# HRV_Control.net
KiCad netlist of a schematic drawn in EAGLE
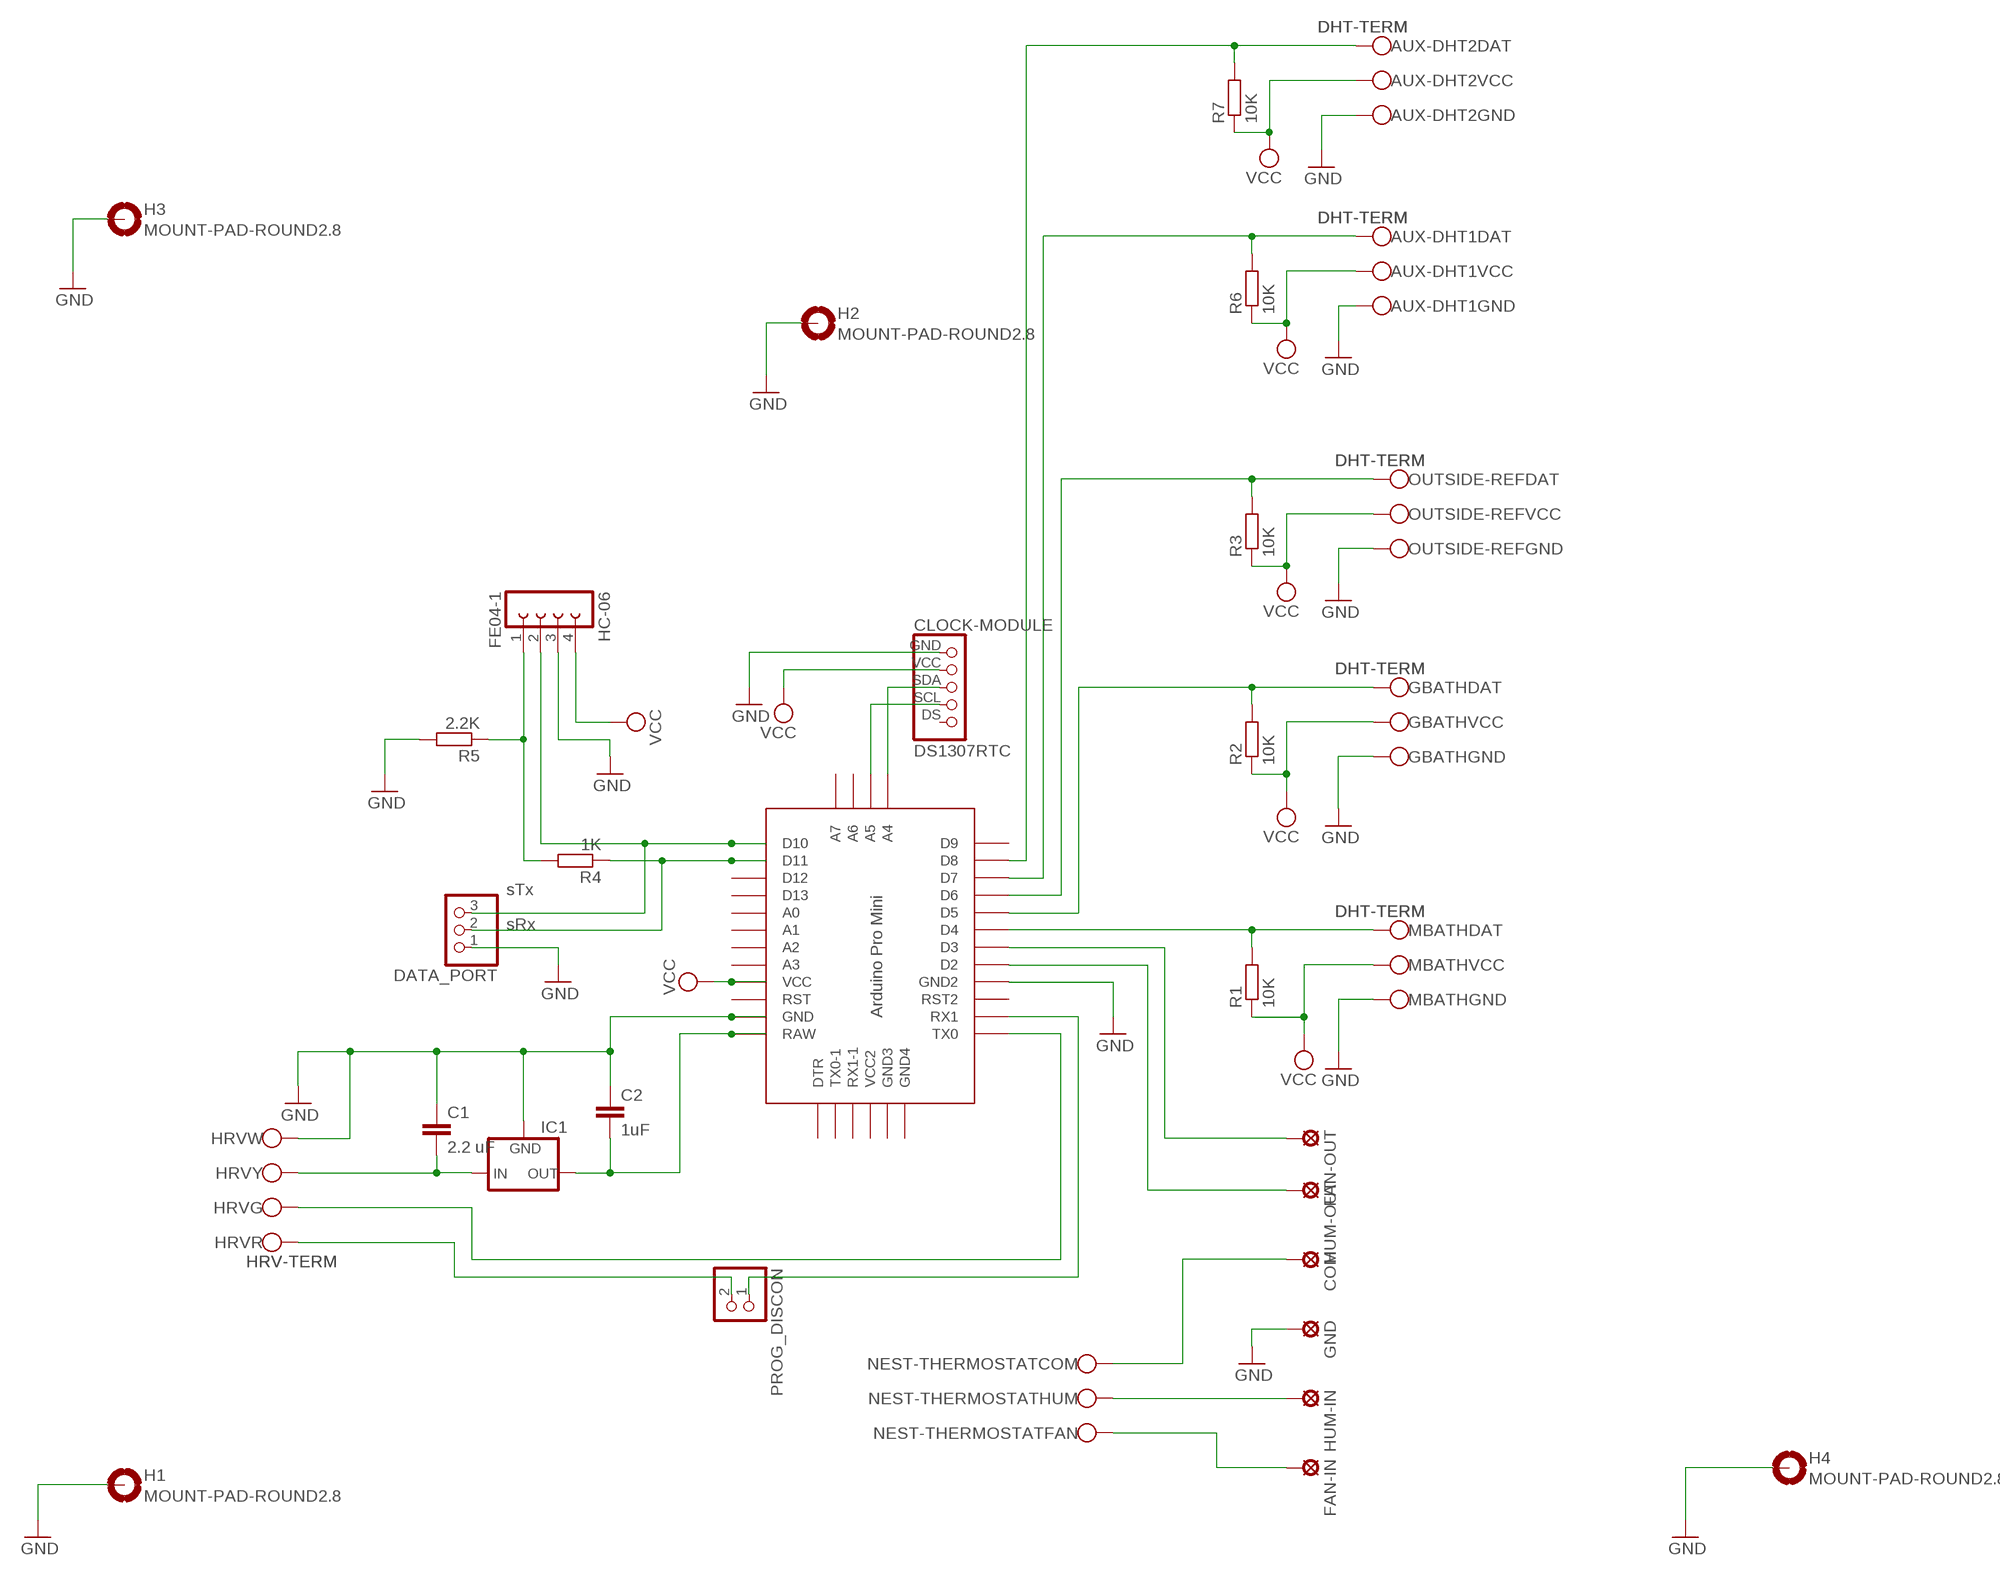
[diagram p0: schematic, sheet 1]

(export (version "E")
  (design (tool "Eeschema 10.0.6"))
  (components
    (comp (ref "AUX-DHT1")
      (value "DHT-TERM")
      (footprint "eagle-import:DHT-TERMINAL")
      (libsource (lib "eagle-import") (part "DHT-TERM"))
    )
    (comp (ref "AUX-DHT2")
      (value "DHT-TERM")
      (footprint "eagle-import:DHT-TERMINAL")
      (libsource (lib "eagle-import") (part "DHT-TERM"))
    )
    (comp (ref "C1")
      (value "2.2 uF")
      (footprint "eagle-import:C5B3")
      (libsource (lib "eagle-import") (part "C5/3"))
    )
    (comp (ref "C2")
      (value "1uF")
      (footprint "eagle-import:C025-024X044")
      (libsource (lib "eagle-import") (part "C-EU025-024X044"))
    )
    (comp (ref "CLOCK-MODULE")
      (value "DS1307RTC")
      (footprint "eagle-import:DS1307RTC")
      (libsource (lib "eagle-import") (part "DS1307RTC"))
    )
    (comp (ref "COM")
      (value "SE14")
      (footprint "eagle-import:SE14")
      (libsource (lib "eagle-import") (part "SE14"))
    )
    (comp (ref "DATA_PORT")
      (value "PINHD-1X3")
      (footprint "eagle-import:1X03")
      (libsource (lib "eagle-import") (part "PINHD-1X3"))
    )
    (comp (ref "FAN-IN")
      (value "SE14")
      (footprint "eagle-import:SE14")
      (libsource (lib "eagle-import") (part "SE14"))
    )
    (comp (ref "FAN-OUT")
      (value "SE14")
      (footprint "eagle-import:SE14")
      (libsource (lib "eagle-import") (part "SE14"))
    )
    (comp (ref "GBATH")
      (value "DHT-TERM")
      (footprint "eagle-import:DHT-TERMINAL")
      (libsource (lib "eagle-import") (part "DHT-TERM"))
    )
    (comp (ref "GND")
      (value "SE14")
      (footprint "eagle-import:SE14")
      (libsource (lib "eagle-import") (part "SE14"))
    )
    (comp (ref "H1")
      (value "MOUNT-PAD-ROUND2.8")
      (footprint "eagle-import:2,8-PAD")
      (libsource (lib "eagle-import") (part "MOUNT-PAD-ROUND2.8"))
    )
    (comp (ref "H2")
      (value "MOUNT-PAD-ROUND2.8")
      (footprint "eagle-import:2,8-PAD")
      (libsource (lib "eagle-import") (part "MOUNT-PAD-ROUND2.8"))
    )
    (comp (ref "H3")
      (value "MOUNT-PAD-ROUND2.8")
      (footprint "eagle-import:2,8-PAD")
      (libsource (lib "eagle-import") (part "MOUNT-PAD-ROUND2.8"))
    )
    (comp (ref "H4")
      (value "MOUNT-PAD-ROUND2.8")
      (footprint "eagle-import:2,8-PAD")
      (libsource (lib "eagle-import") (part "MOUNT-PAD-ROUND2.8"))
    )
    (comp (ref "HC-06")
      (value "FE04-1")
      (footprint "eagle-import:FE04-1")
      (libsource (lib "eagle-import") (part "FE04-1"))
    )
    (comp (ref "HRV")
      (value "HRV-TERM")
      (footprint "eagle-import:HRV-TERM")
      (libsource (lib "eagle-import") (part "HRV-TERM"))
    )
    (comp (ref "HUM-IN")
      (value "SE14")
      (footprint "eagle-import:SE14")
      (libsource (lib "eagle-import") (part "SE14"))
    )
    (comp (ref "HUM-OUT")
      (value "SE14")
      (footprint "eagle-import:SE14")
      (libsource (lib "eagle-import") (part "SE14"))
    )
    (comp (ref "IC1")
      (value "78XXL")
      (footprint "eagle-import:78XXL")
      (libsource (lib "eagle-import") (part "78XXL"))
    )
    (comp (ref "MBATH")
      (value "DHT-TERM")
      (footprint "eagle-import:DHT-TERMINAL")
      (libsource (lib "eagle-import") (part "DHT-TERM"))
    )
    (comp (ref "NEST-THERMOSTAT")
      (value "NEST-TERM")
      (footprint "eagle-import:NEST-TERM")
      (libsource (lib "eagle-import") (part "NEST-TERM"))
    )
    (comp (ref "OUTSIDE-REF")
      (value "DHT-TERM")
      (footprint "eagle-import:DHT-TERMINAL")
      (libsource (lib "eagle-import") (part "DHT-TERM"))
    )
    (comp (ref "PROG_DISCON")
      (value "PINHD-1X2")
      (footprint "eagle-import:1X02")
      (libsource (lib "eagle-import") (part "PINHD-1X2"))
    )
    (comp (ref "R1")
      (value "10K")
      (footprint "eagle-import:0204_7")
      (libsource (lib "eagle-import") (part "R-EU_0204/7"))
    )
    (comp (ref "R2")
      (value "10K")
      (footprint "eagle-import:0204_7")
      (libsource (lib "eagle-import") (part "R-EU_0204/7"))
    )
    (comp (ref "R3")
      (value "10K")
      (footprint "eagle-import:0204_7")
      (libsource (lib "eagle-import") (part "R-EU_0204/7"))
    )
    (comp (ref "R4")
      (value "1K")
      (footprint "eagle-import:0204_7")
      (libsource (lib "eagle-import") (part "R-EU_0204/7"))
    )
    (comp (ref "R5")
      (value "2.2K")
      (footprint "eagle-import:0204_7")
      (libsource (lib "eagle-import") (part "R-EU_0204/7"))
    )
    (comp (ref "R6")
      (value "10K")
      (footprint "eagle-import:0204_7")
      (libsource (lib "eagle-import") (part "R-EU_0204/7"))
    )
    (comp (ref "R7")
      (value "10K")
      (footprint "eagle-import:0204_7")
      (libsource (lib "eagle-import") (part "R-EU_0204/7"))
    )
    (comp (ref "U$6")
      (value "PRO-MINI")
      (footprint "eagle-import:PRO-MINI")
      (libsource (lib "eagle-import") (part "PRO-MINI"))
    )
  )
  (nets
    (net (code "1") (name "GND") (class "Default")
      (node (ref "AUX-DHT1") (pin "GND") (pinfunction "KL_GND") (pintype "passive"))
      (node (ref "AUX-DHT2") (pin "GND") (pinfunction "KL_GND") (pintype "passive"))
      (node (ref "C1") (pin "1") (pinfunction "1_1") (pintype "passive"))
      (node (ref "C2") (pin "1") (pinfunction "1_1") (pintype "passive"))
      (node (ref "CLOCK-MODULE") (pin "GND") (pinfunction "GND_GND") (pintype "passive"))
      (node (ref "DATA_PORT") (pin "1") (pinfunction "1_1") (pintype "passive"))
      (node (ref "GBATH") (pin "GND") (pinfunction "KL_GND") (pintype "passive"))
      (node (ref "GND") (pin "MP") (pinfunction "MP_MP") (pintype "passive"))
      (node (ref "H1") (pin "B2,8") (pinfunction "MOUNT_B2,8") (pintype "passive"))
      (node (ref "H2") (pin "B2,8") (pinfunction "MOUNT_B2,8") (pintype "passive"))
      (node (ref "H3") (pin "B2,8") (pinfunction "MOUNT_B2,8") (pintype "passive"))
      (node (ref "H4") (pin "B2,8") (pinfunction "MOUNT_B2,8") (pintype "passive"))
      (node (ref "HC-06") (pin "3") (pinfunction "3_3") (pintype "passive"))
      (node (ref "HRV") (pin "W") (pinfunction "KL_W") (pintype "passive"))
      (node (ref "IC1") (pin "GND") (pinfunction "GND_GND") (pintype "input"))
      (node (ref "MBATH") (pin "GND") (pinfunction "KL_GND") (pintype "passive"))
      (node (ref "OUTSIDE-REF") (pin "GND") (pinfunction "KL_GND") (pintype "passive"))
      (node (ref "R5") (pin "2") (pinfunction "2_2") (pintype "passive"))
      (node (ref "U$6") (pin "GND") (pinfunction "GND_GND") (pintype "input"))
      (node (ref "U$6") (pin "GND1") (pinfunction "GND2_GND1") (pintype "bidirectional"))
    )
    (net (code "2") (name "Net-(AUX-DHT1A-KL)") (class "Default")
      (node (ref "AUX-DHT1") (pin "DAT") (pinfunction "KL_DAT") (pintype "passive"))
      (node (ref "R6") (pin "2") (pinfunction "2_2") (pintype "passive"))
      (node (ref "U$6") (pin "D7") (pinfunction "D7_D7") (pintype "bidirectional"))
    )
    (net (code "3") (name "Net-(AUX-DHT2A-KL)") (class "Default")
      (node (ref "AUX-DHT2") (pin "DAT") (pinfunction "KL_DAT") (pintype "passive"))
      (node (ref "R7") (pin "2") (pinfunction "2_2") (pintype "passive"))
      (node (ref "U$6") (pin "D8") (pinfunction "D8_D8") (pintype "bidirectional"))
    )
    (net (code "4") (name "Net-(C2-Pad2)") (class "Default")
      (node (ref "C2") (pin "2") (pinfunction "2_2") (pintype "passive"))
      (node (ref "IC1") (pin "OUT") (pinfunction "OUT_OUT") (pintype "passive"))
      (node (ref "U$6") (pin "RAW") (pinfunction "RAW_RAW") (pintype "power_in"))
    )
    (net (code "5") (name "Net-(CLOCK-MODULE-PadSCL)") (class "Default")
      (node (ref "CLOCK-MODULE") (pin "SCL") (pinfunction "SCL_SCL") (pintype "passive"))
      (node (ref "U$6") (pin "A5") (pinfunction "A5_A5") (pintype "bidirectional"))
    )
    (net (code "6") (name "Net-(CLOCK-MODULE-PadSDA)") (class "Default")
      (node (ref "CLOCK-MODULE") (pin "SDA") (pinfunction "SDA_SDA") (pintype "passive"))
      (node (ref "U$6") (pin "A4") (pinfunction "A4_A4") (pintype "bidirectional"))
    )
    (net (code "7") (name "Net-(DATA_PORT-Pad2)") (class "Default")
      (node (ref "DATA_PORT") (pin "2") (pinfunction "2_2") (pintype "passive"))
      (node (ref "R4") (pin "1") (pinfunction "1_1") (pintype "passive"))
      (node (ref "U$6") (pin "D11") (pinfunction "D11_D11") (pintype "bidirectional"))
    )
    (net (code "8") (name "Net-(DATA_PORT-Pad3)") (class "Default")
      (node (ref "DATA_PORT") (pin "3") (pinfunction "3_3") (pintype "passive"))
      (node (ref "HC-06") (pin "2") (pinfunction "2_2") (pintype "passive"))
      (node (ref "U$6") (pin "D10") (pinfunction "D10_D10") (pintype "bidirectional"))
    )
    (net (code "9") (name "Net-(FAN-OUT-PadMP)") (class "Default")
      (node (ref "FAN-OUT") (pin "MP") (pinfunction "MP_MP") (pintype "passive"))
      (node (ref "U$6") (pin "D3") (pinfunction "D3_D3") (pintype "bidirectional"))
    )
    (net (code "10") (name "Net-(GBATHA-KL)") (class "Default")
      (node (ref "GBATH") (pin "DAT") (pinfunction "KL_DAT") (pintype "passive"))
      (node (ref "R2") (pin "2") (pinfunction "2_2") (pintype "passive"))
      (node (ref "U$6") (pin "D5") (pinfunction "D5_D5") (pintype "bidirectional"))
    )
    (net (code "11") (name "Net-(HC-06-Pad1)") (class "Default")
      (node (ref "HC-06") (pin "1") (pinfunction "1_1") (pintype "passive"))
      (node (ref "R4") (pin "2") (pinfunction "2_2") (pintype "passive"))
      (node (ref "R5") (pin "1") (pinfunction "1_1") (pintype "passive"))
    )
    (net (code "12") (name "Net-(HRVA-KL)") (class "Default")
      (node (ref "HRV") (pin "G") (pinfunction "KL_G") (pintype "passive"))
      (node (ref "U$6") (pin "TX0") (pinfunction "TX0_TX0") (pintype "bidirectional"))
    )
    (net (code "13") (name "Net-(HRVB-KL)") (class "Default")
      (node (ref "HRV") (pin "R") (pinfunction "KL_R") (pintype "passive"))
      (node (ref "PROG_DISCON") (pin "2") (pinfunction "2_2") (pintype "passive"))
    )
    (net (code "14") (name "Net-(HRVD-KL)") (class "Default")
      (node (ref "C1") (pin "2") (pinfunction "2_2") (pintype "passive"))
      (node (ref "HRV") (pin "Y") (pinfunction "KL_Y") (pintype "passive"))
      (node (ref "IC1") (pin "IN") (pinfunction "IN_IN") (pintype "input"))
    )
    (net (code "15") (name "Net-(HUM-OUT-PadMP)") (class "Default")
      (node (ref "HUM-OUT") (pin "MP") (pinfunction "MP_MP") (pintype "passive"))
      (node (ref "U$6") (pin "D2") (pinfunction "D2_D2") (pintype "bidirectional"))
    )
    (net (code "16") (name "Net-(MBATHA-KL)") (class "Default")
      (node (ref "MBATH") (pin "DAT") (pinfunction "KL_DAT") (pintype "passive"))
      (node (ref "R1") (pin "2") (pinfunction "2_2") (pintype "passive"))
      (node (ref "U$6") (pin "D4") (pinfunction "D4_D4") (pintype "bidirectional"))
    )
    (net (code "17") (name "Net-(NEST-THERMOSTATA-KL)") (class "Default")
      (node (ref "COM") (pin "MP") (pinfunction "MP_MP") (pintype "passive"))
      (node (ref "NEST-THERMOSTAT") (pin "COM") (pinfunction "KL_COM") (pintype "passive"))
    )
    (net (code "18") (name "Net-(NEST-THERMOSTATB-KL)") (class "Default")
      (node (ref "FAN-IN") (pin "MP") (pinfunction "MP_MP") (pintype "passive"))
      (node (ref "NEST-THERMOSTAT") (pin "FAN") (pinfunction "KL_FAN") (pintype "passive"))
    )
    (net (code "19") (name "Net-(NEST-THERMOSTATC-KL)") (class "Default")
      (node (ref "HUM-IN") (pin "MP") (pinfunction "MP_MP") (pintype "passive"))
      (node (ref "NEST-THERMOSTAT") (pin "HUM") (pinfunction "KL_HUM") (pintype "passive"))
    )
    (net (code "20") (name "Net-(OUTSIDE-REFA-KL)") (class "Default")
      (node (ref "OUTSIDE-REF") (pin "DAT") (pinfunction "KL_DAT") (pintype "passive"))
      (node (ref "R3") (pin "2") (pinfunction "2_2") (pintype "passive"))
      (node (ref "U$6") (pin "D6") (pinfunction "D6_D6") (pintype "bidirectional"))
    )
    (net (code "21") (name "Net-(PROG_DISCON-Pad1)") (class "Default")
      (node (ref "PROG_DISCON") (pin "1") (pinfunction "1_1") (pintype "passive"))
      (node (ref "U$6") (pin "RX1") (pinfunction "RX1_RX1") (pintype "bidirectional"))
    )
    (net (code "22") (name "VCC") (class "Default")
      (node (ref "AUX-DHT1") (pin "VCC") (pinfunction "KL_VCC") (pintype "passive"))
      (node (ref "AUX-DHT2") (pin "VCC") (pinfunction "KL_VCC") (pintype "passive"))
      (node (ref "CLOCK-MODULE") (pin "VCC") (pinfunction "VCC_VCC") (pintype "passive"))
      (node (ref "GBATH") (pin "VCC") (pinfunction "KL_VCC") (pintype "passive"))
      (node (ref "HC-06") (pin "4") (pinfunction "4_4") (pintype "passive"))
      (node (ref "MBATH") (pin "VCC") (pinfunction "KL_VCC") (pintype "passive"))
      (node (ref "OUTSIDE-REF") (pin "VCC") (pinfunction "KL_VCC") (pintype "passive"))
      (node (ref "R1") (pin "1") (pinfunction "1_1") (pintype "passive"))
      (node (ref "R2") (pin "1") (pinfunction "1_1") (pintype "passive"))
      (node (ref "R3") (pin "1") (pinfunction "1_1") (pintype "passive"))
      (node (ref "R6") (pin "1") (pinfunction "1_1") (pintype "passive"))
      (node (ref "R7") (pin "1") (pinfunction "1_1") (pintype "passive"))
      (node (ref "U$6") (pin "VCC") (pinfunction "VCC_VCC") (pintype "bidirectional"))
    )
    (net (code "23") (name "unconnected-(CLOCK-MODULE-PadDS)") (class "Default")
      (node (ref "CLOCK-MODULE") (pin "DS") (pinfunction "DS_DS") (pintype "passive"))
    )
    (net (code "24") (name "unconnected-(U$6-GND4-PadGND2)") (class "Default")
      (node (ref "U$6") (pin "GND2") (pinfunction "GND4_GND2") (pintype "bidirectional"))
    )
    (net (code "25") (name "unconnected-(U$6-PadA0)") (class "Default")
      (node (ref "U$6") (pin "A0") (pinfunction "A0_A0") (pintype "bidirectional"))
    )
    (net (code "26") (name "unconnected-(U$6-PadA1)") (class "Default")
      (node (ref "U$6") (pin "A1") (pinfunction "A1_A1") (pintype "bidirectional"))
    )
    (net (code "27") (name "unconnected-(U$6-PadA2)") (class "Default")
      (node (ref "U$6") (pin "A2") (pinfunction "A2_A2") (pintype "bidirectional"))
    )
    (net (code "28") (name "unconnected-(U$6-PadA3)") (class "Default")
      (node (ref "U$6") (pin "A3") (pinfunction "A3_A3") (pintype "bidirectional"))
    )
    (net (code "29") (name "unconnected-(U$6-PadA6)") (class "Default")
      (node (ref "U$6") (pin "A6") (pinfunction "A6_A6") (pintype "bidirectional"))
    )
    (net (code "30") (name "unconnected-(U$6-PadA7)") (class "Default")
      (node (ref "U$6") (pin "A7") (pinfunction "A7_A7") (pintype "bidirectional"))
    )
    (net (code "31") (name "unconnected-(U$6-PadD9)") (class "Default")
      (node (ref "U$6") (pin "D9") (pinfunction "D9_D9") (pintype "bidirectional"))
    )
    (net (code "32") (name "unconnected-(U$6-PadD12)") (class "Default")
      (node (ref "U$6") (pin "D12") (pinfunction "D12_D12") (pintype "bidirectional"))
    )
    (net (code "33") (name "unconnected-(U$6-PadD13)") (class "Default")
      (node (ref "U$6") (pin "D13") (pinfunction "D13_D13") (pintype "bidirectional"))
    )
    (net (code "34") (name "unconnected-(U$6-PadDTR)") (class "Default")
      (node (ref "U$6") (pin "DTR") (pinfunction "DTR_DTR") (pintype "bidirectional"))
    )
    (net (code "35") (name "unconnected-(U$6-PadGND3)") (class "Default")
      (node (ref "U$6") (pin "GND3") (pinfunction "GND3_GND3") (pintype "bidirectional"))
    )
    (net (code "36") (name "unconnected-(U$6-PadRST)") (class "Default")
      (node (ref "U$6") (pin "RST") (pinfunction "RST_RST") (pintype "bidirectional"))
    )
    (net (code "37") (name "unconnected-(U$6-PadRX1-1)") (class "Default")
      (node (ref "U$6") (pin "RX1-1") (pinfunction "RX1-1_RX1-1") (pintype "bidirectional"))
    )
    (net (code "38") (name "unconnected-(U$6-PadTX0-1)") (class "Default")
      (node (ref "U$6") (pin "TX0-1") (pinfunction "TX0-1_TX0-1") (pintype "bidirectional"))
    )
    (net (code "39") (name "unconnected-(U$6-RST2-PadRST1)") (class "Default")
      (node (ref "U$6") (pin "RST1") (pinfunction "RST2_RST1") (pintype "bidirectional"))
    )
    (net (code "40") (name "unconnected-(U$6-VCC2-PadVCC1)") (class "Default")
      (node (ref "U$6") (pin "VCC1") (pinfunction "VCC2_VCC1") (pintype "bidirectional"))
    )
  )
)
